# ETH.net
KiCad netlist of a schematic drawn in Altium Designer
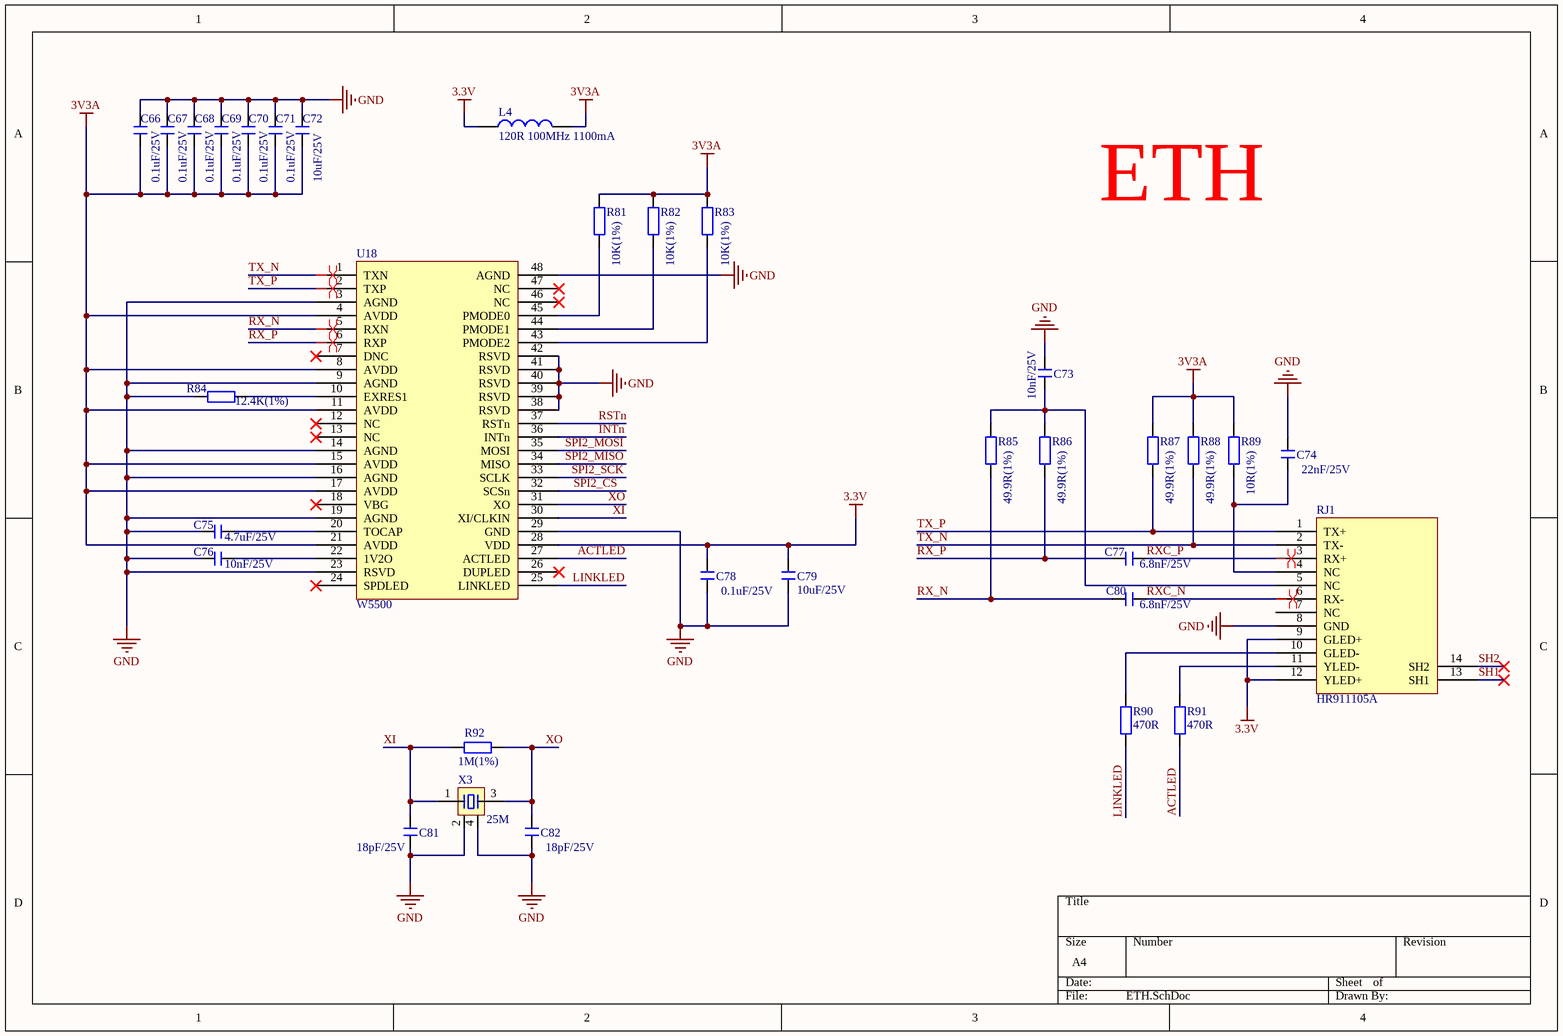
[diagram p0: ETH.SchDoc]

(export (version "E")
  (design (tool "Eeschema 10.0.6"))
  (components
    (comp (ref "C66")
      (value "0.1uF/25V")
      (footprint "C 0603_L")
      (description "无极性贴片电容")
      (fields (field (name "版权归属") "源创客"))
      (libsource (lib "电阻-电容-电感") (part "C"))
    )
    (comp (ref "C67")
      (value "0.1uF/25V")
      (footprint "C 0603_L")
      (description "无极性贴片电容")
      (fields (field (name "版权归属") "源创客"))
      (libsource (lib "电阻-电容-电感") (part "C"))
    )
    (comp (ref "C68")
      (value "0.1uF/25V")
      (footprint "C 0603_L")
      (description "无极性贴片电容")
      (fields (field (name "版权归属") "源创客"))
      (libsource (lib "电阻-电容-电感") (part "C"))
    )
    (comp (ref "C69")
      (value "0.1uF/25V")
      (footprint "C 0603_L")
      (description "无极性贴片电容")
      (fields (field (name "版权归属") "源创客"))
      (libsource (lib "电阻-电容-电感") (part "C"))
    )
    (comp (ref "C70")
      (value "0.1uF/25V")
      (footprint "C 0603_L")
      (description "无极性贴片电容")
      (fields (field (name "版权归属") "源创客"))
      (libsource (lib "电阻-电容-电感") (part "C"))
    )
    (comp (ref "C71")
      (value "0.1uF/25V")
      (footprint "C 0603_L")
      (description "无极性贴片电容")
      (fields (field (name "版权归属") "源创客"))
      (libsource (lib "电阻-电容-电感") (part "C"))
    )
    (comp (ref "C72")
      (value "10uF/25V")
      (footprint "C 0603_L")
      (description "无极性贴片电容")
      (fields (field (name "版权归属") "源创客"))
      (libsource (lib "电阻-电容-电感") (part "C"))
    )
    (comp (ref "C73")
      (value "10nF/25V")
      (footprint "C 0603_L")
      (description "无极性贴片电容")
      (fields (field (name "版权归属") "源创客"))
      (libsource (lib "电阻-电容-电感") (part "C"))
    )
    (comp (ref "C74")
      (value "22nF/25V")
      (footprint "C 0603_L")
      (description "无极性贴片电容")
      (fields (field (name "版权归属") "源创客"))
      (libsource (lib "电阻-电容-电感") (part "C"))
    )
    (comp (ref "C75")
      (value "4.7uF/25V")
      (footprint "C 0603_L")
      (description "无极性贴片电容")
      (fields (field (name "版权归属") "源创客"))
      (libsource (lib "电阻-电容-电感") (part "C"))
    )
    (comp (ref "C76")
      (value "10nF/25V")
      (footprint "C 0603_L")
      (description "无极性贴片电容")
      (fields (field (name "版权归属") "源创客"))
      (libsource (lib "电阻-电容-电感") (part "C"))
    )
    (comp (ref "C77")
      (value "6.8nF/25V")
      (footprint "C 0603_L")
      (description "无极性贴片电容")
      (fields (field (name "版权归属") "源创客"))
      (libsource (lib "电阻-电容-电感") (part "C"))
    )
    (comp (ref "C78")
      (value "0.1uF/25V")
      (footprint "C 0603_L")
      (description "无极性贴片电容")
      (fields (field (name "版权归属") "源创客"))
      (libsource (lib "电阻-电容-电感") (part "C"))
    )
    (comp (ref "C79")
      (value "10uF/25V")
      (footprint "C 0603_L")
      (description "无极性贴片电容")
      (fields (field (name "版权归属") "源创客"))
      (libsource (lib "电阻-电容-电感") (part "C"))
    )
    (comp (ref "C80")
      (value "6.8nF/25V")
      (footprint "C 0603_L")
      (description "无极性贴片电容")
      (fields (field (name "版权归属") "源创客"))
      (libsource (lib "电阻-电容-电感") (part "C"))
    )
    (comp (ref "C81")
      (value "18pF/25V")
      (footprint "C 0603_L")
      (description "无极性贴片电容")
      (fields (field (name "版权归属") "源创客"))
      (libsource (lib "电阻-电容-电感") (part "C"))
    )
    (comp (ref "C82")
      (value "18pF/25V")
      (footprint "C 0603_L")
      (description "无极性贴片电容")
      (fields (field (name "版权归属") "源创客"))
      (libsource (lib "电阻-电容-电感") (part "C"))
    )
    (comp (ref "L4")
      (value "120R 100MHz 1100mA")
      (footprint "L 0603")
      (description "磁珠 HH-1M1608-121JT")
      (fields (field (name "版权归属") "源创客"))
      (libsource (lib "电阻-电容-电感") (part "L"))
    )
    (comp (ref "R81")
      (value "10K(1%)")
      (footprint "R 0603_L")
      (description "贴片电阻")
      (fields (field (name "版权归属") "源创客"))
      (libsource (lib "电阻-电容-电感") (part "R"))
    )
    (comp (ref "R82")
      (value "10K(1%)")
      (footprint "R 0603_L")
      (description "贴片电阻")
      (fields (field (name "版权归属") "源创客"))
      (libsource (lib "电阻-电容-电感") (part "R"))
    )
    (comp (ref "R83")
      (value "10K(1%)")
      (footprint "R 0603_L")
      (description "贴片电阻")
      (fields (field (name "版权归属") "源创客"))
      (libsource (lib "电阻-电容-电感") (part "R"))
    )
    (comp (ref "R84")
      (value "12.4K(1%)")
      (footprint "R 0603_L")
      (description "贴片电阻")
      (fields (field (name "版权归属") "源创客"))
      (libsource (lib "电阻-电容-电感") (part "R"))
    )
    (comp (ref "R85")
      (value "49.9R(1%)")
      (footprint "R 0603_L")
      (description "贴片电阻")
      (fields (field (name "版权归属") "源创客"))
      (libsource (lib "电阻-电容-电感") (part "R"))
    )
    (comp (ref "R86")
      (value "49.9R(1%)")
      (footprint "R 0603_L")
      (description "贴片电阻")
      (fields (field (name "版权归属") "源创客"))
      (libsource (lib "电阻-电容-电感") (part "R"))
    )
    (comp (ref "R87")
      (value "49.9R(1%)")
      (footprint "R 0603_L")
      (description "贴片电阻")
      (fields (field (name "版权归属") "源创客"))
      (libsource (lib "电阻-电容-电感") (part "R"))
    )
    (comp (ref "R88")
      (value "49.9R(1%)")
      (footprint "R 0603_L")
      (description "贴片电阻")
      (fields (field (name "版权归属") "源创客"))
      (libsource (lib "电阻-电容-电感") (part "R"))
    )
    (comp (ref "R89")
      (value "10R(1%)")
      (footprint "R 0603_L")
      (description "贴片电阻")
      (fields (field (name "版权归属") "源创客"))
      (libsource (lib "电阻-电容-电感") (part "R"))
    )
    (comp (ref "R90")
      (value "470R")
      (footprint "R 0603_L")
      (description "贴片电阻")
      (fields (field (name "版权归属") "源创客"))
      (libsource (lib "电阻-电容-电感") (part "R"))
    )
    (comp (ref "R91")
      (value "470R")
      (footprint "R 0603_L")
      (description "贴片电阻")
      (fields (field (name "版权归属") "源创客"))
      (libsource (lib "电阻-电容-电感") (part "R"))
    )
    (comp (ref "R92")
      (value "1M(1%)")
      (footprint "R 0603_L")
      (description "贴片电阻")
      (fields (field (name "版权归属") "源创客"))
      (libsource (lib "电阻-电容-电感") (part "R"))
    )
    (comp (ref "RJ1")
      (value "HR911105A")
      (footprint "RJ-45A12")
      (description "带灯以太网接口")
      (libsource (lib "MICB") (part "HR911105A"))
    )
    (comp (ref "U18") (value "W5500") (footprint "LQFP48 7X7_N") (libsource (lib "MICB") (part "W5500")))
    (comp (ref "X3")
      (value "25M")
      (footprint "OSC 3225-4P")
      (description "4脚无源晶振")
      (fields (field (name "版权归属") "源创客"))
      (libsource (lib "保险丝-晶振") (part "XTAL-4P"))
    )
  )
  (nets
    (net (code "1") (name "/ACTLED") (class "Default")
      (node (ref "R91") (pin "2") (pinfunction "2_2") (pintype "passive"))
      (node (ref "U18") (pin "27") (pinfunction "ACTLED_27") (pintype "passive"))
    )
    (net (code "2") (name "/INTn") (class "Default")
      (node (ref "U18") (pin "36") (pinfunction "INTn_36") (pintype "passive"))
    )
    (net (code "3") (name "/LINKLED") (class "Default")
      (node (ref "R90") (pin "2") (pinfunction "2_2") (pintype "passive"))
      (node (ref "U18") (pin "25") (pinfunction "LINKLED_25") (pintype "passive"))
    )
    (net (code "4") (name "/RSTn") (class "Default")
      (node (ref "U18") (pin "37") (pinfunction "RSTn_37") (pintype "passive"))
    )
    (net (code "5") (name "/RXC_N") (class "Default")
      (node (ref "C80") (pin "2") (pinfunction "2_2") (pintype "passive"))
      (node (ref "RJ1") (pin "6") (pinfunction "RX-_6") (pintype "passive"))
    )
    (net (code "6") (name "/RXC_P") (class "Default")
      (node (ref "C77") (pin "2") (pinfunction "2_2") (pintype "passive"))
      (node (ref "RJ1") (pin "3") (pinfunction "RX+_3") (pintype "passive"))
    )
    (net (code "7") (name "/RX_N") (class "Default")
      (node (ref "C80") (pin "1") (pinfunction "1_1") (pintype "passive"))
      (node (ref "R85") (pin "2") (pinfunction "2_2") (pintype "passive"))
      (node (ref "U18") (pin "5") (pinfunction "RXN_5") (pintype "passive"))
    )
    (net (code "8") (name "/RX_P") (class "Default")
      (node (ref "C77") (pin "1") (pinfunction "1_1") (pintype "passive"))
      (node (ref "R86") (pin "2") (pinfunction "2_2") (pintype "passive"))
      (node (ref "U18") (pin "6") (pinfunction "RXP_6") (pintype "passive"))
    )
    (net (code "9") (name "/SH1") (class "Default")
      (node (ref "RJ1") (pin "13") (pinfunction "SH1_13") (pintype "passive+no_connect"))
    )
    (net (code "10") (name "/SH2") (class "Default")
      (node (ref "RJ1") (pin "14") (pinfunction "SH2_14") (pintype "passive+no_connect"))
    )
    (net (code "11") (name "/SPI2_CS") (class "Default")
      (node (ref "U18") (pin "32") (pinfunction "SCSn_32") (pintype "passive"))
    )
    (net (code "12") (name "/SPI2_MISO") (class "Default")
      (node (ref "U18") (pin "34") (pinfunction "MISO_34") (pintype "passive"))
    )
    (net (code "13") (name "/SPI2_MOSI") (class "Default")
      (node (ref "U18") (pin "35") (pinfunction "MOSI_35") (pintype "passive"))
    )
    (net (code "14") (name "/SPI2_SCK") (class "Default")
      (node (ref "U18") (pin "33") (pinfunction "SCLK_33") (pintype "passive"))
    )
    (net (code "15") (name "/TX_N") (class "Default")
      (node (ref "R88") (pin "2") (pinfunction "2_2") (pintype "passive"))
      (node (ref "RJ1") (pin "2") (pinfunction "TX-_2") (pintype "passive"))
      (node (ref "U18") (pin "1") (pinfunction "TXN_1") (pintype "passive"))
    )
    (net (code "16") (name "/TX_P") (class "Default")
      (node (ref "R87") (pin "2") (pinfunction "2_2") (pintype "passive"))
      (node (ref "RJ1") (pin "1") (pinfunction "TX+_1") (pintype "passive"))
      (node (ref "U18") (pin "2") (pinfunction "TXP_2") (pintype "passive"))
    )
    (net (code "17") (name "/XI") (class "Default")
      (node (ref "C81") (pin "1") (pinfunction "1_1") (pintype "passive"))
      (node (ref "R92") (pin "2") (pinfunction "2_2") (pintype "passive"))
      (node (ref "U18") (pin "30") (pinfunction "XI/CLKIN_30") (pintype "passive"))
      (node (ref "X3") (pin "1") (pinfunction "1_1") (pintype "passive"))
    )
    (net (code "18") (name "/XO") (class "Default")
      (node (ref "C82") (pin "1") (pinfunction "1_1") (pintype "passive"))
      (node (ref "R92") (pin "1") (pinfunction "1_1") (pintype "passive"))
      (node (ref "U18") (pin "31") (pinfunction "XO_31") (pintype "passive"))
      (node (ref "X3") (pin "3") (pinfunction "3_3") (pintype "passive"))
    )
    (net (code "19") (name "3.3V") (class "Default")
      (node (ref "C78") (pin "1") (pinfunction "1_1") (pintype "passive"))
      (node (ref "C79") (pin "1") (pinfunction "1_1") (pintype "passive"))
      (node (ref "L4") (pin "1") (pinfunction "1_1") (pintype "passive"))
      (node (ref "RJ1") (pin "12") (pinfunction "YLED+_12") (pintype "passive"))
      (node (ref "RJ1") (pin "9") (pinfunction "GLED+_9") (pintype "passive"))
      (node (ref "U18") (pin "28") (pinfunction "VDD_28") (pintype "passive"))
    )
    (net (code "20") (name "3V3A") (class "Default")
      (node (ref "C66") (pin "2") (pinfunction "2_2") (pintype "passive"))
      (node (ref "C67") (pin "2") (pinfunction "2_2") (pintype "passive"))
      (node (ref "C68") (pin "2") (pinfunction "2_2") (pintype "passive"))
      (node (ref "C69") (pin "2") (pinfunction "2_2") (pintype "passive"))
      (node (ref "C70") (pin "2") (pinfunction "2_2") (pintype "passive"))
      (node (ref "C71") (pin "2") (pinfunction "2_2") (pintype "passive"))
      (node (ref "C72") (pin "2") (pinfunction "2_2") (pintype "passive"))
      (node (ref "L4") (pin "2") (pinfunction "2_2") (pintype "passive"))
      (node (ref "R81") (pin "1") (pinfunction "1_1") (pintype "passive"))
      (node (ref "R82") (pin "1") (pinfunction "1_1") (pintype "passive"))
      (node (ref "R83") (pin "1") (pinfunction "1_1") (pintype "passive"))
      (node (ref "R87") (pin "1") (pinfunction "1_1") (pintype "passive"))
      (node (ref "R88") (pin "1") (pinfunction "1_1") (pintype "passive"))
      (node (ref "R89") (pin "1") (pinfunction "1_1") (pintype "passive"))
      (node (ref "U18") (pin "11") (pinfunction "AVDD_11") (pintype "passive"))
      (node (ref "U18") (pin "15") (pinfunction "AVDD_15") (pintype "passive"))
      (node (ref "U18") (pin "17") (pinfunction "AVDD_17") (pintype "passive"))
      (node (ref "U18") (pin "21") (pinfunction "AVDD_21") (pintype "passive"))
      (node (ref "U18") (pin "4") (pinfunction "AVDD_4") (pintype "passive"))
      (node (ref "U18") (pin "8") (pinfunction "AVDD_8") (pintype "passive"))
    )
    (net (code "21") (name "GND") (class "Default")
      (node (ref "C66") (pin "1") (pinfunction "1_1") (pintype "passive"))
      (node (ref "C67") (pin "1") (pinfunction "1_1") (pintype "passive"))
      (node (ref "C68") (pin "1") (pinfunction "1_1") (pintype "passive"))
      (node (ref "C69") (pin "1") (pinfunction "1_1") (pintype "passive"))
      (node (ref "C70") (pin "1") (pinfunction "1_1") (pintype "passive"))
      (node (ref "C71") (pin "1") (pinfunction "1_1") (pintype "passive"))
      (node (ref "C72") (pin "1") (pinfunction "1_1") (pintype "passive"))
      (node (ref "C73") (pin "1") (pinfunction "1_1") (pintype "passive"))
      (node (ref "C74") (pin "1") (pinfunction "1_1") (pintype "passive"))
      (node (ref "C75") (pin "2") (pinfunction "2_2") (pintype "passive"))
      (node (ref "C76") (pin "2") (pinfunction "2_2") (pintype "passive"))
      (node (ref "C78") (pin "2") (pinfunction "2_2") (pintype "passive"))
      (node (ref "C79") (pin "2") (pinfunction "2_2") (pintype "passive"))
      (node (ref "C81") (pin "2") (pinfunction "2_2") (pintype "passive"))
      (node (ref "C82") (pin "2") (pinfunction "2_2") (pintype "passive"))
      (node (ref "R84") (pin "2") (pinfunction "2_2") (pintype "passive"))
      (node (ref "RJ1") (pin "8") (pinfunction "GND_8") (pintype "passive"))
      (node (ref "U18") (pin "14") (pinfunction "AGND_14") (pintype "passive"))
      (node (ref "U18") (pin "16") (pinfunction "AGND_16") (pintype "passive"))
      (node (ref "U18") (pin "19") (pinfunction "AGND_19") (pintype "passive"))
      (node (ref "U18") (pin "23") (pinfunction "RSVD_23") (pintype "passive"))
      (node (ref "U18") (pin "29") (pinfunction "GND_29") (pintype "passive"))
      (node (ref "U18") (pin "3") (pinfunction "AGND_3") (pintype "passive"))
      (node (ref "U18") (pin "38") (pinfunction "RSVD_38") (pintype "passive"))
      (node (ref "U18") (pin "39") (pinfunction "RSVD_39") (pintype "passive"))
      (node (ref "U18") (pin "40") (pinfunction "RSVD_40") (pintype "passive"))
      (node (ref "U18") (pin "41") (pinfunction "RSVD_41") (pintype "passive"))
      (node (ref "U18") (pin "42") (pinfunction "RSVD_42") (pintype "passive"))
      (node (ref "U18") (pin "48") (pinfunction "AGND_48") (pintype "passive"))
      (node (ref "U18") (pin "9") (pinfunction "AGND_9") (pintype "passive"))
      (node (ref "X3") (pin "2") (pinfunction "2_2") (pintype "passive"))
      (node (ref "X3") (pin "4") (pinfunction "4_4") (pintype "passive"))
    )
    (net (code "22") (name "Net-(C73-Pad2)") (class "Default")
      (node (ref "C73") (pin "2") (pinfunction "2_2") (pintype "passive"))
      (node (ref "R85") (pin "1") (pinfunction "1_1") (pintype "passive"))
      (node (ref "R86") (pin "1") (pinfunction "1_1") (pintype "passive"))
      (node (ref "RJ1") (pin "5") (pinfunction "NC_5") (pintype "passive"))
    )
    (net (code "23") (name "Net-(C74-Pad2)") (class "Default")
      (node (ref "C74") (pin "2") (pinfunction "2_2") (pintype "passive"))
      (node (ref "R89") (pin "2") (pinfunction "2_2") (pintype "passive"))
      (node (ref "RJ1") (pin "4") (pinfunction "NC_4") (pintype "passive"))
    )
    (net (code "24") (name "Net-(RJ1-GLED-)") (class "Default")
      (node (ref "R90") (pin "1") (pinfunction "1_1") (pintype "passive"))
      (node (ref "RJ1") (pin "10") (pinfunction "GLED-_10") (pintype "passive"))
    )
    (net (code "25") (name "Net-(RJ1-YLED-)") (class "Default")
      (node (ref "R91") (pin "1") (pinfunction "1_1") (pintype "passive"))
      (node (ref "RJ1") (pin "11") (pinfunction "YLED-_11") (pintype "passive"))
    )
    (net (code "26") (name "Net-(U18-1V2O)") (class "Default")
      (node (ref "C76") (pin "1") (pinfunction "1_1") (pintype "passive"))
      (node (ref "U18") (pin "22") (pinfunction "1V2O_22") (pintype "passive"))
    )
    (net (code "27") (name "Net-(U18-EXRES1)") (class "Default")
      (node (ref "R84") (pin "1") (pinfunction "1_1") (pintype "passive"))
      (node (ref "U18") (pin "10") (pinfunction "EXRES1_10") (pintype "passive"))
    )
    (net (code "28") (name "Net-(U18-PMODE0)") (class "Default")
      (node (ref "R81") (pin "2") (pinfunction "2_2") (pintype "passive"))
      (node (ref "U18") (pin "45") (pinfunction "PMODE0_45") (pintype "passive"))
    )
    (net (code "29") (name "Net-(U18-PMODE1)") (class "Default")
      (node (ref "R82") (pin "2") (pinfunction "2_2") (pintype "passive"))
      (node (ref "U18") (pin "44") (pinfunction "PMODE1_44") (pintype "passive"))
    )
    (net (code "30") (name "Net-(U18-PMODE2)") (class "Default")
      (node (ref "R83") (pin "2") (pinfunction "2_2") (pintype "passive"))
      (node (ref "U18") (pin "43") (pinfunction "PMODE2_43") (pintype "passive"))
    )
    (net (code "31") (name "Net-(U18-TOCAP)") (class "Default")
      (node (ref "C75") (pin "1") (pinfunction "1_1") (pintype "passive"))
      (node (ref "U18") (pin "20") (pinfunction "TOCAP_20") (pintype "passive"))
    )
    (net (code "32") (name "unconnected-(RJ1-NC-Pad7)") (class "Default")
      (node (ref "RJ1") (pin "7") (pinfunction "NC_7") (pintype "passive"))
    )
    (net (code "33") (name "unconnected-(U18-DNC-Pad7)") (class "Default")
      (node (ref "U18") (pin "7") (pinfunction "DNC_7") (pintype "passive+no_connect"))
    )
    (net (code "34") (name "unconnected-(U18-DUPLED-Pad26)") (class "Default")
      (node (ref "U18") (pin "26") (pinfunction "DUPLED_26") (pintype "passive+no_connect"))
    )
    (net (code "35") (name "unconnected-(U18-NC-Pad12)") (class "Default")
      (node (ref "U18") (pin "12") (pinfunction "NC_12") (pintype "passive+no_connect"))
    )
    (net (code "36") (name "unconnected-(U18-NC-Pad13)") (class "Default")
      (node (ref "U18") (pin "13") (pinfunction "NC_13") (pintype "passive+no_connect"))
    )
    (net (code "37") (name "unconnected-(U18-NC-Pad46)") (class "Default")
      (node (ref "U18") (pin "46") (pinfunction "NC_46") (pintype "passive+no_connect"))
    )
    (net (code "38") (name "unconnected-(U18-NC-Pad47)") (class "Default")
      (node (ref "U18") (pin "47") (pinfunction "NC_47") (pintype "passive+no_connect"))
    )
    (net (code "39") (name "unconnected-(U18-SPDLED-Pad24)") (class "Default")
      (node (ref "U18") (pin "24") (pinfunction "SPDLED_24") (pintype "passive+no_connect"))
    )
    (net (code "40") (name "unconnected-(U18-VBG-Pad18)") (class "Default")
      (node (ref "U18") (pin "18") (pinfunction "VBG_18") (pintype "passive+no_connect"))
    )
  )
)
